# STM32_IO.net
KiCad netlist of a schematic drawn in Altium Designer
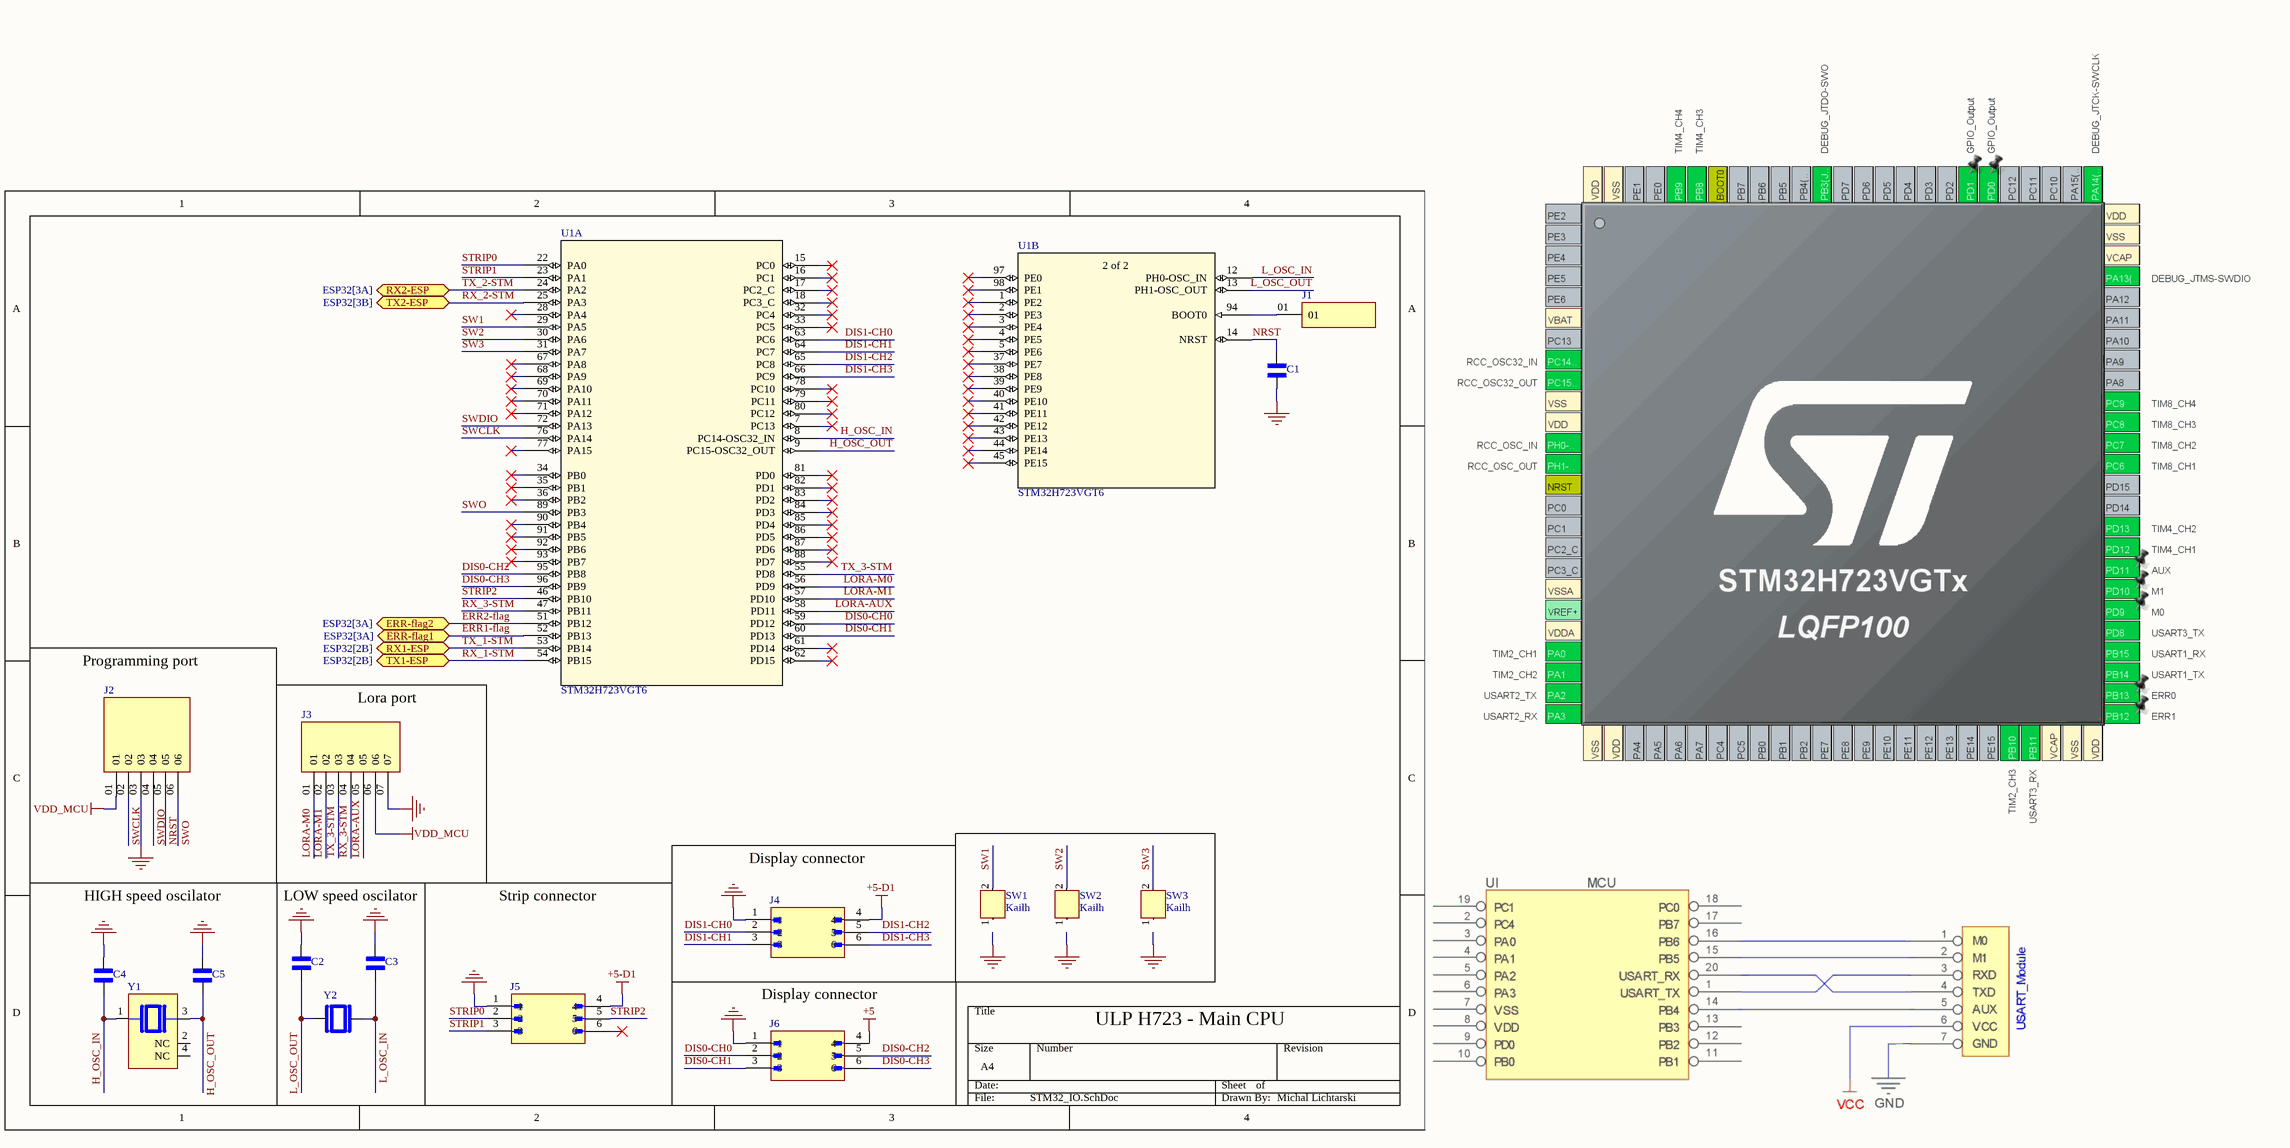
[diagram p0: STM32_IO.SchDoc]

(export (version "E")
  (design (tool "Eeschema 10.0.6"))
  (components
    (comp (ref "C1")
      (value "CL10C180JB8NNNC")
      (footprint "CL10A105KA8NNNC:CAPC1608X90N")
      (description "100nF 0603")
      (fields
        (field (name "MF") "{'manufacturer': u'Samsung Electro-Mechanics'}")
        (field (name "MP") "CL10A105KA8NNNC")
      )
      (libsource (lib "*") (part "CL10A105KA8NNNC"))
    )
    (comp (ref "C2")
      (value "CL10C180JB8NNNC")
      (footprint "CL10A105KA8NNNC:CAPC1608X90N")
      (description "18pf 0603")
      (fields
        (field (name "MF") "{'manufacturer': u'Samsung Electro-Mechanics'}")
        (field (name "MP") "CL10A105KA8NNNC")
      )
      (libsource (lib "*") (part "CL10A105KA8NNNC"))
    )
    (comp (ref "C3")
      (value "CL10C180JB8NNNC")
      (footprint "CL10A105KA8NNNC:CAPC1608X90N")
      (description "18pf 0603")
      (fields
        (field (name "MF") "{'manufacturer': u'Samsung Electro-Mechanics'}")
        (field (name "MP") "CL10A105KA8NNNC")
      )
      (libsource (lib "*") (part "CL10A105KA8NNNC"))
    )
    (comp (ref "C4")
      (value "CL10C100JB8NNNC")
      (footprint "CL10A105KA8NNNC:CAPC1608X90N")
      (description "18pf 0603")
      (fields
        (field (name "MF") "{'manufacturer': u'Samsung Electro-Mechanics'}")
        (field (name "MP") "CL10A105KA8NNNC")
      )
      (libsource (lib "*") (part "CL10A105KA8NNNC"))
    )
    (comp (ref "C5")
      (value "CL10C100JB8NNNC")
      (footprint "CL10A105KA8NNNC:CAPC1608X90N")
      (description "18pf 0603")
      (fields
        (field (name "MF") "{'manufacturer': u'Samsung Electro-Mechanics'}")
        (field (name "MP") "CL10A105KA8NNNC")
      )
      (libsource (lib "*") (part "CL10A105KA8NNNC"))
    )
    (comp (ref "J1")
      (value "TSW-101-07-G-S")
      (footprint "TSW-101-07-G-S:SAMTEC_TSW-101-07-G-S")
      (fields (field (name "MF") "{'manufacturer': u'Samtec Inc.'}"))
      (libsource (lib "*") (part "TSW-101-07-G-S"))
    )
    (comp (ref "J2")
      (value "TSW-106-07-G-S")
      (footprint "TSW-106-07-G-S:SAMTEC_TSW-106-07-G-S")
      (fields (field (name "MF") "{'manufacturer': u'Samtec Inc.'}"))
      (libsource (lib "*") (part "TSW-106-07-G-S"))
    )
    (comp (ref "J3")
      (value "TSW-107-07-G-S")
      (footprint "TSW-107-07-G-S:SAMTEC_TSW-107-07-G-S")
      (fields (field (name "MF") "{'manufacturer': u'Samtec Inc.'}"))
      (libsource (lib "*") (part "TSW-107-07-G-S"))
    )
    (comp (ref "J4")
      (value "874270602")
      (footprint "MOLEX_874270602")
      (libsource (lib "874270602") (part "874270602"))
    )
    (comp (ref "J5")
      (value "874270602")
      (footprint "MOLEX_874270602")
      (libsource (lib "874270602") (part "874270602"))
    )
    (comp (ref "J6")
      (value "874270602")
      (footprint "MOLEX_874270602")
      (libsource (lib "874270602") (part "874270602"))
    )
    (comp (ref "SW1")
      (value "Kailh")
      (footprint "SW_MX_reversible")
      (description "Kailh mechanical switch")
      (libsource (lib "Kailh") (part "Component_1"))
    )
    (comp (ref "SW2")
      (value "Kailh")
      (footprint "SW_MX_reversible")
      (description "Kailh mechanical switch")
      (libsource (lib "Kailh") (part "Component_1"))
    )
    (comp (ref "SW3")
      (value "Kailh")
      (footprint "SW_MX_reversible")
      (description "Kailh mechanical switch")
      (libsource (lib "Kailh") (part "Component_1"))
    )
    (comp (ref "U1")
      (value "STM32H723VGT6")
      (footprint "LQFP100_STM")
      (description "No Description Available")
      (fields (field (name "COPYRIGHT") "Copyright (C) 2023 Ultra Librarian. All rights reserved."))
      (libsource (lib "STM32H723VGT6") (part "STM32H723VGT6"))
    )
    (comp (ref "Y1")
      (value "QT325G-25.000MEEV-T")
      (footprint "XTAL_QT325G-25.000MEEV-T")
      (description "25 MHz Â±10ppm Crystal 8pF 60 Ohms 4-SMD, No Lead")
      (fields (field (name "MF") "QST PRODUCTS LLC"))
      (libsource (lib "QT325G-25.000MEEV-T") (part "QT325G-25.000MEEV-T"))
    )
    (comp (ref "Y2")
      (value "ABS07-32.768KHZ-T")
      (footprint "ABS07-32.768KHZ-T:XTAL_ABS07-32.768KHZ-T")
      (fields (field (name "MF") "{'manufacturer': u'SHENZHEN YANGXING TECHNOLOGY CO., LTD.'}"))
      (libsource (lib "*") (part "ABS07-32.768KHZ-T"))
    )
  )
  (nets
    (net (code "1") (name "+5") (class "Default")
      (node (ref "J6") (pin "4") (pinfunction "4_4") (pintype "passive"))
    )
    (net (code "2") (name "+5-D1") (class "Default")
      (node (ref "J4") (pin "4") (pinfunction "4_4") (pintype "passive"))
      (node (ref "J5") (pin "4") (pinfunction "4_4") (pintype "passive"))
    )
    (net (code "3") (name "/DIS0-CH0") (class "Default")
      (node (ref "J6") (pin "2") (pinfunction "2_2") (pintype "passive"))
      (node (ref "U1") (pin "59") (pinfunction "PD12_59") (pintype "bidirectional"))
    )
    (net (code "4") (name "/DIS0-CH1") (class "Default")
      (node (ref "J6") (pin "3") (pinfunction "3_3") (pintype "passive"))
      (node (ref "U1") (pin "60") (pinfunction "PD13_60") (pintype "bidirectional"))
    )
    (net (code "5") (name "/DIS0-CH2") (class "Default")
      (node (ref "J6") (pin "5") (pinfunction "5_5") (pintype "passive"))
      (node (ref "U1") (pin "95") (pinfunction "PB8_95") (pintype "bidirectional"))
    )
    (net (code "6") (name "/DIS0-CH3") (class "Default")
      (node (ref "J6") (pin "6") (pinfunction "6_6") (pintype "passive"))
      (node (ref "U1") (pin "96") (pinfunction "PB9_96") (pintype "bidirectional"))
    )
    (net (code "7") (name "/DIS1-CH0") (class "Default")
      (node (ref "J4") (pin "2") (pinfunction "2_2") (pintype "passive"))
      (node (ref "U1") (pin "63") (pinfunction "PC6_63") (pintype "bidirectional"))
    )
    (net (code "8") (name "/DIS1-CH1") (class "Default")
      (node (ref "J4") (pin "3") (pinfunction "3_3") (pintype "passive"))
      (node (ref "U1") (pin "64") (pinfunction "PC7_64") (pintype "bidirectional"))
    )
    (net (code "9") (name "/DIS1-CH2") (class "Default")
      (node (ref "J4") (pin "5") (pinfunction "5_5") (pintype "passive"))
      (node (ref "U1") (pin "65") (pinfunction "PC8_65") (pintype "bidirectional"))
    )
    (net (code "10") (name "/DIS1-CH3") (class "Default")
      (node (ref "J4") (pin "6") (pinfunction "6_6") (pintype "passive"))
      (node (ref "U1") (pin "66") (pinfunction "PC9_66") (pintype "bidirectional"))
    )
    (net (code "11") (name "/ERR1-flag") (class "Default")
      (node (ref "U1") (pin "52") (pinfunction "PB13_52") (pintype "bidirectional"))
    )
    (net (code "12") (name "/ERR2-flag") (class "Default")
      (node (ref "U1") (pin "51") (pinfunction "PB12_51") (pintype "bidirectional"))
    )
    (net (code "13") (name "/H_OSC_IN") (class "Default")
      (node (ref "C4") (pin "2") (pinfunction "2_2") (pintype "passive"))
      (node (ref "U1") (pin "8") (pinfunction "PC14-OSC32_IN_8") (pintype "bidirectional"))
      (node (ref "Y1") (pin "1") (pinfunction "1_1") (pintype "passive"))
    )
    (net (code "14") (name "/H_OSC_OUT") (class "Default")
      (node (ref "C5") (pin "2") (pinfunction "2_2") (pintype "passive"))
      (node (ref "U1") (pin "9") (pinfunction "PC15-OSC32_OUT_9") (pintype "bidirectional"))
      (node (ref "Y1") (pin "3") (pinfunction "2_3") (pintype "passive"))
    )
    (net (code "15") (name "/LORA-AUX") (class "Default")
      (node (ref "J3") (pin "05") (pinfunction "05_05") (pintype "passive"))
      (node (ref "U1") (pin "58") (pinfunction "PD11_58") (pintype "bidirectional"))
    )
    (net (code "16") (name "/LORA-M0") (class "Default")
      (node (ref "J3") (pin "01") (pinfunction "01_01") (pintype "passive"))
      (node (ref "U1") (pin "56") (pinfunction "PD9_56") (pintype "bidirectional"))
    )
    (net (code "17") (name "/LORA-M1") (class "Default")
      (node (ref "J3") (pin "02") (pinfunction "02_02") (pintype "passive"))
      (node (ref "U1") (pin "57") (pinfunction "PD10_57") (pintype "bidirectional"))
    )
    (net (code "18") (name "/L_OSC_IN") (class "Default")
      (node (ref "C3") (pin "2") (pinfunction "2_2") (pintype "passive"))
      (node (ref "U1") (pin "12") (pinfunction "PH0-OSC_IN_12") (pintype "bidirectional"))
      (node (ref "Y2") (pin "2") (pinfunction "2_2") (pintype "passive"))
    )
    (net (code "19") (name "/L_OSC_OUT") (class "Default")
      (node (ref "C2") (pin "2") (pinfunction "2_2") (pintype "passive"))
      (node (ref "U1") (pin "13") (pinfunction "PH1-OSC_OUT_13") (pintype "bidirectional"))
      (node (ref "Y2") (pin "1") (pinfunction "1_1") (pintype "passive"))
    )
    (net (code "20") (name "/NRST") (class "Default")
      (node (ref "C1") (pin "1") (pinfunction "1_1") (pintype "passive"))
      (node (ref "J2") (pin "05") (pinfunction "05_05") (pintype "passive"))
      (node (ref "U1") (pin "14") (pinfunction "NRST_14") (pintype "bidirectional"))
    )
    (net (code "21") (name "/RX_1-STM") (class "Default")
      (node (ref "U1") (pin "54") (pinfunction "PB15_54") (pintype "bidirectional"))
    )
    (net (code "22") (name "/RX_2-STM") (class "Default")
      (node (ref "U1") (pin "25") (pinfunction "PA3_25") (pintype "bidirectional"))
    )
    (net (code "23") (name "/RX_3-STM") (class "Default")
      (node (ref "J3") (pin "04") (pinfunction "04_04") (pintype "passive"))
      (node (ref "U1") (pin "47") (pinfunction "PB11_47") (pintype "bidirectional"))
    )
    (net (code "24") (name "/STRIP0") (class "Default")
      (node (ref "J5") (pin "2") (pinfunction "2_2") (pintype "passive"))
      (node (ref "U1") (pin "22") (pinfunction "PA0_22") (pintype "bidirectional"))
    )
    (net (code "25") (name "/STRIP1") (class "Default")
      (node (ref "J5") (pin "3") (pinfunction "3_3") (pintype "passive"))
      (node (ref "U1") (pin "23") (pinfunction "PA1_23") (pintype "bidirectional"))
    )
    (net (code "26") (name "/STRIP2") (class "Default")
      (node (ref "J5") (pin "5") (pinfunction "5_5") (pintype "passive"))
      (node (ref "U1") (pin "46") (pinfunction "PB10_46") (pintype "bidirectional"))
    )
    (net (code "27") (name "/SW1") (class "Default")
      (node (ref "SW1") (pin "2") (pintype "bidirectional"))
      (node (ref "U1") (pin "29") (pinfunction "PA5_29") (pintype "bidirectional"))
    )
    (net (code "28") (name "/SW2") (class "Default")
      (node (ref "SW2") (pin "2") (pintype "bidirectional"))
      (node (ref "U1") (pin "30") (pinfunction "PA6_30") (pintype "bidirectional"))
    )
    (net (code "29") (name "/SW3") (class "Default")
      (node (ref "SW3") (pin "2") (pintype "bidirectional"))
      (node (ref "U1") (pin "31") (pinfunction "PA7_31") (pintype "bidirectional"))
    )
    (net (code "30") (name "/SWCLK") (class "Default")
      (node (ref "J2") (pin "02") (pinfunction "02_02") (pintype "passive"))
      (node (ref "U1") (pin "76") (pinfunction "PA14_76") (pintype "bidirectional"))
    )
    (net (code "31") (name "/SWDIO") (class "Default")
      (node (ref "J2") (pin "04") (pinfunction "04_04") (pintype "passive"))
      (node (ref "U1") (pin "72") (pinfunction "PA13_72") (pintype "bidirectional"))
    )
    (net (code "32") (name "/SWO") (class "Default")
      (node (ref "J2") (pin "06") (pinfunction "06_06") (pintype "passive"))
      (node (ref "U1") (pin "89") (pinfunction "PB3_89") (pintype "bidirectional"))
    )
    (net (code "33") (name "/TX_1-STM") (class "Default")
      (node (ref "U1") (pin "53") (pinfunction "PB14_53") (pintype "bidirectional"))
    )
    (net (code "34") (name "/TX_2-STM") (class "Default")
      (node (ref "U1") (pin "24") (pinfunction "PA2_24") (pintype "bidirectional"))
    )
    (net (code "35") (name "/TX_3-STM") (class "Default")
      (node (ref "J3") (pin "03") (pinfunction "03_03") (pintype "passive"))
      (node (ref "U1") (pin "55") (pinfunction "PD8_55") (pintype "bidirectional"))
    )
    (net (code "36") (name "GND") (class "Default")
      (node (ref "C1") (pin "2") (pinfunction "2_2") (pintype "passive"))
      (node (ref "C2") (pin "1") (pinfunction "1_1") (pintype "passive"))
      (node (ref "C3") (pin "1") (pinfunction "1_1") (pintype "passive"))
      (node (ref "C4") (pin "1") (pinfunction "1_1") (pintype "passive"))
      (node (ref "C5") (pin "1") (pinfunction "1_1") (pintype "passive"))
      (node (ref "J2") (pin "03") (pinfunction "03_03") (pintype "passive"))
      (node (ref "J3") (pin "07") (pinfunction "07_07") (pintype "passive"))
      (node (ref "J4") (pin "1") (pinfunction "1_1") (pintype "passive"))
      (node (ref "J5") (pin "1") (pinfunction "1_1") (pintype "passive"))
      (node (ref "J6") (pin "1") (pinfunction "1_1") (pintype "passive"))
    )
    (net (code "37") (name "Net-(U1B-BOOT0)") (class "Default")
      (node (ref "J1") (pin "01") (pinfunction "01_01") (pintype "passive"))
      (node (ref "U1") (pin "94") (pinfunction "BOOT0_94") (pintype "input"))
    )
    (net (code "38") (name "VDD_MCU") (class "Default")
      (node (ref "J2") (pin "01") (pinfunction "01_01") (pintype "passive"))
      (node (ref "J3") (pin "06") (pinfunction "06_06") (pintype "passive"))
    )
    (net (code "39") (name "unconnected-(J5-Pad6)") (class "Default")
      (node (ref "J5") (pin "6") (pinfunction "6_6") (pintype "passive+no_connect"))
    )
    (net (code "40") (name "unconnected-(SW1-Pad1)") (class "Default")
      (node (ref "SW1") (pin "1") (pintype "bidirectional"))
    )
    (net (code "41") (name "unconnected-(SW2-Pad1)") (class "Default")
      (node (ref "SW2") (pin "1") (pintype "bidirectional"))
    )
    (net (code "42") (name "unconnected-(SW3-Pad1)") (class "Default")
      (node (ref "SW3") (pin "1") (pintype "bidirectional"))
    )
    (net (code "43") (name "unconnected-(U1A-PA4-Pad28)") (class "Default")
      (node (ref "U1") (pin "28") (pinfunction "PA4_28") (pintype "bidirectional+no_connect"))
    )
    (net (code "44") (name "unconnected-(U1A-PA8-Pad67)") (class "Default")
      (node (ref "U1") (pin "67") (pinfunction "PA8_67") (pintype "bidirectional+no_connect"))
    )
    (net (code "45") (name "unconnected-(U1A-PA9-Pad68)") (class "Default")
      (node (ref "U1") (pin "68") (pinfunction "PA9_68") (pintype "bidirectional+no_connect"))
    )
    (net (code "46") (name "unconnected-(U1A-PA10-Pad69)") (class "Default")
      (node (ref "U1") (pin "69") (pinfunction "PA10_69") (pintype "bidirectional+no_connect"))
    )
    (net (code "47") (name "unconnected-(U1A-PA11-Pad70)") (class "Default")
      (node (ref "U1") (pin "70") (pinfunction "PA11_70") (pintype "bidirectional+no_connect"))
    )
    (net (code "48") (name "unconnected-(U1A-PA12-Pad71)") (class "Default")
      (node (ref "U1") (pin "71") (pinfunction "PA12_71") (pintype "bidirectional+no_connect"))
    )
    (net (code "49") (name "unconnected-(U1A-PA15-Pad77)") (class "Default")
      (node (ref "U1") (pin "77") (pinfunction "PA15_77") (pintype "bidirectional+no_connect"))
    )
    (net (code "50") (name "unconnected-(U1A-PB0-Pad34)") (class "Default")
      (node (ref "U1") (pin "34") (pinfunction "PB0_34") (pintype "bidirectional+no_connect"))
    )
    (net (code "51") (name "unconnected-(U1A-PB1-Pad35)") (class "Default")
      (node (ref "U1") (pin "35") (pinfunction "PB1_35") (pintype "bidirectional+no_connect"))
    )
    (net (code "52") (name "unconnected-(U1A-PB2-Pad36)") (class "Default")
      (node (ref "U1") (pin "36") (pinfunction "PB2_36") (pintype "bidirectional+no_connect"))
    )
    (net (code "53") (name "unconnected-(U1A-PB4-Pad90)") (class "Default")
      (node (ref "U1") (pin "90") (pinfunction "PB4_90") (pintype "bidirectional+no_connect"))
    )
    (net (code "54") (name "unconnected-(U1A-PB5-Pad91)") (class "Default")
      (node (ref "U1") (pin "91") (pinfunction "PB5_91") (pintype "bidirectional+no_connect"))
    )
    (net (code "55") (name "unconnected-(U1A-PB6-Pad92)") (class "Default")
      (node (ref "U1") (pin "92") (pinfunction "PB6_92") (pintype "bidirectional+no_connect"))
    )
    (net (code "56") (name "unconnected-(U1A-PB7-Pad93)") (class "Default")
      (node (ref "U1") (pin "93") (pinfunction "PB7_93") (pintype "bidirectional+no_connect"))
    )
    (net (code "57") (name "unconnected-(U1A-PC0-Pad15)") (class "Default")
      (node (ref "U1") (pin "15") (pinfunction "PC0_15") (pintype "bidirectional+no_connect"))
    )
    (net (code "58") (name "unconnected-(U1A-PC1-Pad16)") (class "Default")
      (node (ref "U1") (pin "16") (pinfunction "PC1_16") (pintype "bidirectional+no_connect"))
    )
    (net (code "59") (name "unconnected-(U1A-PC2_C-Pad17)") (class "Default")
      (node (ref "U1") (pin "17") (pinfunction "PC2_C_17") (pintype "bidirectional+no_connect"))
    )
    (net (code "60") (name "unconnected-(U1A-PC3_C-Pad18)") (class "Default")
      (node (ref "U1") (pin "18") (pinfunction "PC3_C_18") (pintype "bidirectional+no_connect"))
    )
    (net (code "61") (name "unconnected-(U1A-PC4-Pad32)") (class "Default")
      (node (ref "U1") (pin "32") (pinfunction "PC4_32") (pintype "bidirectional+no_connect"))
    )
    (net (code "62") (name "unconnected-(U1A-PC5-Pad33)") (class "Default")
      (node (ref "U1") (pin "33") (pinfunction "PC5_33") (pintype "bidirectional+no_connect"))
    )
    (net (code "63") (name "unconnected-(U1A-PC10-Pad78)") (class "Default")
      (node (ref "U1") (pin "78") (pinfunction "PC10_78") (pintype "bidirectional+no_connect"))
    )
    (net (code "64") (name "unconnected-(U1A-PC11-Pad79)") (class "Default")
      (node (ref "U1") (pin "79") (pinfunction "PC11_79") (pintype "bidirectional+no_connect"))
    )
    (net (code "65") (name "unconnected-(U1A-PC12-Pad80)") (class "Default")
      (node (ref "U1") (pin "80") (pinfunction "PC12_80") (pintype "bidirectional+no_connect"))
    )
    (net (code "66") (name "unconnected-(U1A-PC13-Pad7)") (class "Default")
      (node (ref "U1") (pin "7") (pinfunction "PC13_7") (pintype "bidirectional+no_connect"))
    )
    (net (code "67") (name "unconnected-(U1A-PD0-Pad81)") (class "Default")
      (node (ref "U1") (pin "81") (pinfunction "PD0_81") (pintype "bidirectional+no_connect"))
    )
    (net (code "68") (name "unconnected-(U1A-PD1-Pad82)") (class "Default")
      (node (ref "U1") (pin "82") (pinfunction "PD1_82") (pintype "bidirectional+no_connect"))
    )
    (net (code "69") (name "unconnected-(U1A-PD2-Pad83)") (class "Default")
      (node (ref "U1") (pin "83") (pinfunction "PD2_83") (pintype "bidirectional+no_connect"))
    )
    (net (code "70") (name "unconnected-(U1A-PD3-Pad84)") (class "Default")
      (node (ref "U1") (pin "84") (pinfunction "PD3_84") (pintype "bidirectional+no_connect"))
    )
    (net (code "71") (name "unconnected-(U1A-PD4-Pad85)") (class "Default")
      (node (ref "U1") (pin "85") (pinfunction "PD4_85") (pintype "bidirectional+no_connect"))
    )
    (net (code "72") (name "unconnected-(U1A-PD5-Pad86)") (class "Default")
      (node (ref "U1") (pin "86") (pinfunction "PD5_86") (pintype "bidirectional+no_connect"))
    )
    (net (code "73") (name "unconnected-(U1A-PD6-Pad87)") (class "Default")
      (node (ref "U1") (pin "87") (pinfunction "PD6_87") (pintype "bidirectional+no_connect"))
    )
    (net (code "74") (name "unconnected-(U1A-PD7-Pad88)") (class "Default")
      (node (ref "U1") (pin "88") (pinfunction "PD7_88") (pintype "bidirectional+no_connect"))
    )
    (net (code "75") (name "unconnected-(U1A-PD14-Pad61)") (class "Default")
      (node (ref "U1") (pin "61") (pinfunction "PD14_61") (pintype "bidirectional+no_connect"))
    )
    (net (code "76") (name "unconnected-(U1A-PD15-Pad62)") (class "Default")
      (node (ref "U1") (pin "62") (pinfunction "PD15_62") (pintype "bidirectional+no_connect"))
    )
    (net (code "77") (name "unconnected-(U1B-PE0-Pad97)") (class "Default")
      (node (ref "U1") (pin "97") (pinfunction "PE0_97") (pintype "bidirectional+no_connect"))
    )
    (net (code "78") (name "unconnected-(U1B-PE1-Pad98)") (class "Default")
      (node (ref "U1") (pin "98") (pinfunction "PE1_98") (pintype "bidirectional+no_connect"))
    )
    (net (code "79") (name "unconnected-(U1B-PE2-Pad1)") (class "Default")
      (node (ref "U1") (pin "1") (pinfunction "PE2_1") (pintype "bidirectional+no_connect"))
    )
    (net (code "80") (name "unconnected-(U1B-PE3-Pad2)") (class "Default")
      (node (ref "U1") (pin "2") (pinfunction "PE3_2") (pintype "bidirectional+no_connect"))
    )
    (net (code "81") (name "unconnected-(U1B-PE4-Pad3)") (class "Default")
      (node (ref "U1") (pin "3") (pinfunction "PE4_3") (pintype "bidirectional+no_connect"))
    )
    (net (code "82") (name "unconnected-(U1B-PE5-Pad4)") (class "Default")
      (node (ref "U1") (pin "4") (pinfunction "PE5_4") (pintype "bidirectional+no_connect"))
    )
    (net (code "83") (name "unconnected-(U1B-PE6-Pad5)") (class "Default")
      (node (ref "U1") (pin "5") (pinfunction "PE6_5") (pintype "bidirectional+no_connect"))
    )
    (net (code "84") (name "unconnected-(U1B-PE7-Pad37)") (class "Default")
      (node (ref "U1") (pin "37") (pinfunction "PE7_37") (pintype "bidirectional+no_connect"))
    )
    (net (code "85") (name "unconnected-(U1B-PE8-Pad38)") (class "Default")
      (node (ref "U1") (pin "38") (pinfunction "PE8_38") (pintype "bidirectional+no_connect"))
    )
    (net (code "86") (name "unconnected-(U1B-PE9-Pad39)") (class "Default")
      (node (ref "U1") (pin "39") (pinfunction "PE9_39") (pintype "bidirectional+no_connect"))
    )
    (net (code "87") (name "unconnected-(U1B-PE10-Pad40)") (class "Default")
      (node (ref "U1") (pin "40") (pinfunction "PE10_40") (pintype "bidirectional+no_connect"))
    )
    (net (code "88") (name "unconnected-(U1B-PE11-Pad41)") (class "Default")
      (node (ref "U1") (pin "41") (pinfunction "PE11_41") (pintype "bidirectional+no_connect"))
    )
    (net (code "89") (name "unconnected-(U1B-PE12-Pad42)") (class "Default")
      (node (ref "U1") (pin "42") (pinfunction "PE12_42") (pintype "bidirectional+no_connect"))
    )
    (net (code "90") (name "unconnected-(U1B-PE13-Pad43)") (class "Default")
      (node (ref "U1") (pin "43") (pinfunction "PE13_43") (pintype "bidirectional+no_connect"))
    )
    (net (code "91") (name "unconnected-(U1B-PE14-Pad44)") (class "Default")
      (node (ref "U1") (pin "44") (pinfunction "PE14_44") (pintype "bidirectional+no_connect"))
    )
    (net (code "92") (name "unconnected-(U1B-PE15-Pad45)") (class "Default")
      (node (ref "U1") (pin "45") (pinfunction "PE15_45") (pintype "bidirectional+no_connect"))
    )
    (net (code "93") (name "unconnected-(Y1-NC-Pad2)") (class "Default")
      (node (ref "Y1") (pin "2") (pinfunction "NC_2") (pintype "passive"))
    )
    (net (code "94") (name "unconnected-(Y1-NC-Pad4)") (class "Default")
      (node (ref "Y1") (pin "4") (pinfunction "NC_4") (pintype "passive"))
    )
  )
)
